# head.net
KiCad netlist of a schematic drawn in EAGLE
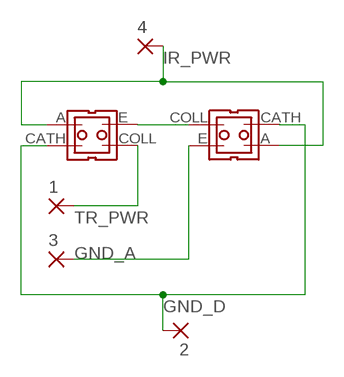
[diagram p0: schematic, sheet 1]

(export (version "E")
  (design (tool "Eeschema 10.0.6"))
  (components
    (comp (ref "1")
      (value "2,15/1,0")
      (footprint "eagle-import:2,15_1,0")
      (libsource (lib "eagle-import") (part "2,15/1,0"))
    )
    (comp (ref "2")
      (value "2,15/1,0")
      (footprint "eagle-import:2,15_1,0")
      (libsource (lib "eagle-import") (part "2,15/1,0"))
    )
    (comp (ref "3")
      (value "2,15/1,0")
      (footprint "eagle-import:2,15_1,0")
      (libsource (lib "eagle-import") (part "2,15/1,0"))
    )
    (comp (ref "4")
      (value "2,15/1,0")
      (footprint "eagle-import:2,15_1,0")
      (libsource (lib "eagle-import") (part "2,15/1,0"))
    )
    (comp (ref "U$1")
      (value "CNY70")
      (footprint "eagle-import:CNY70")
      (libsource (lib "eagle-import") (part "CNY70"))
    )
    (comp (ref "U$2")
      (value "CNY70")
      (footprint "eagle-import:CNY70")
      (libsource (lib "eagle-import") (part "CNY70"))
    )
  )
  (nets
    (net (code "1") (name "/GND_A") (class "Default")
      (node (ref "3") (pin "1") (pinfunction "P_1") (pintype "passive"))
      (node (ref "U$2") (pin "E") (pinfunction "GND(PWR)_E") (pintype "power_in"))
    )
    (net (code "2") (name "/GND_D") (class "Default")
      (node (ref "2") (pin "1") (pinfunction "P_1") (pintype "passive"))
      (node (ref "U$1") (pin "CATH") (pinfunction "GND(DIG)_CATH") (pintype "power_in"))
      (node (ref "U$2") (pin "CATH") (pinfunction "GND(DIG)_CATH") (pintype "power_in"))
    )
    (net (code "3") (name "/IR_PWR") (class "Default")
      (node (ref "4") (pin "1") (pinfunction "P_1") (pintype "passive"))
      (node (ref "U$1") (pin "A") (pinfunction "5V(DIG)_A") (pintype "power_in"))
      (node (ref "U$2") (pin "A") (pinfunction "5V(DIG)_A") (pintype "power_in"))
    )
    (net (code "4") (name "/TR_PWR") (class "Default")
      (node (ref "1") (pin "1") (pinfunction "P_1") (pintype "passive"))
      (node (ref "U$1") (pin "COLL") (pinfunction "5V(PWR)_COLL") (pintype "power_in"))
    )
    (net (code "5") (name "Net-(U$1-GND(PWR))") (class "Default")
      (node (ref "U$1") (pin "E") (pinfunction "GND(PWR)_E") (pintype "power_in"))
      (node (ref "U$2") (pin "COLL") (pinfunction "5V(PWR)_COLL") (pintype "power_in"))
    )
  )
)
